# LEDBox.net
KiCad netlist of a schematic drawn in EAGLE
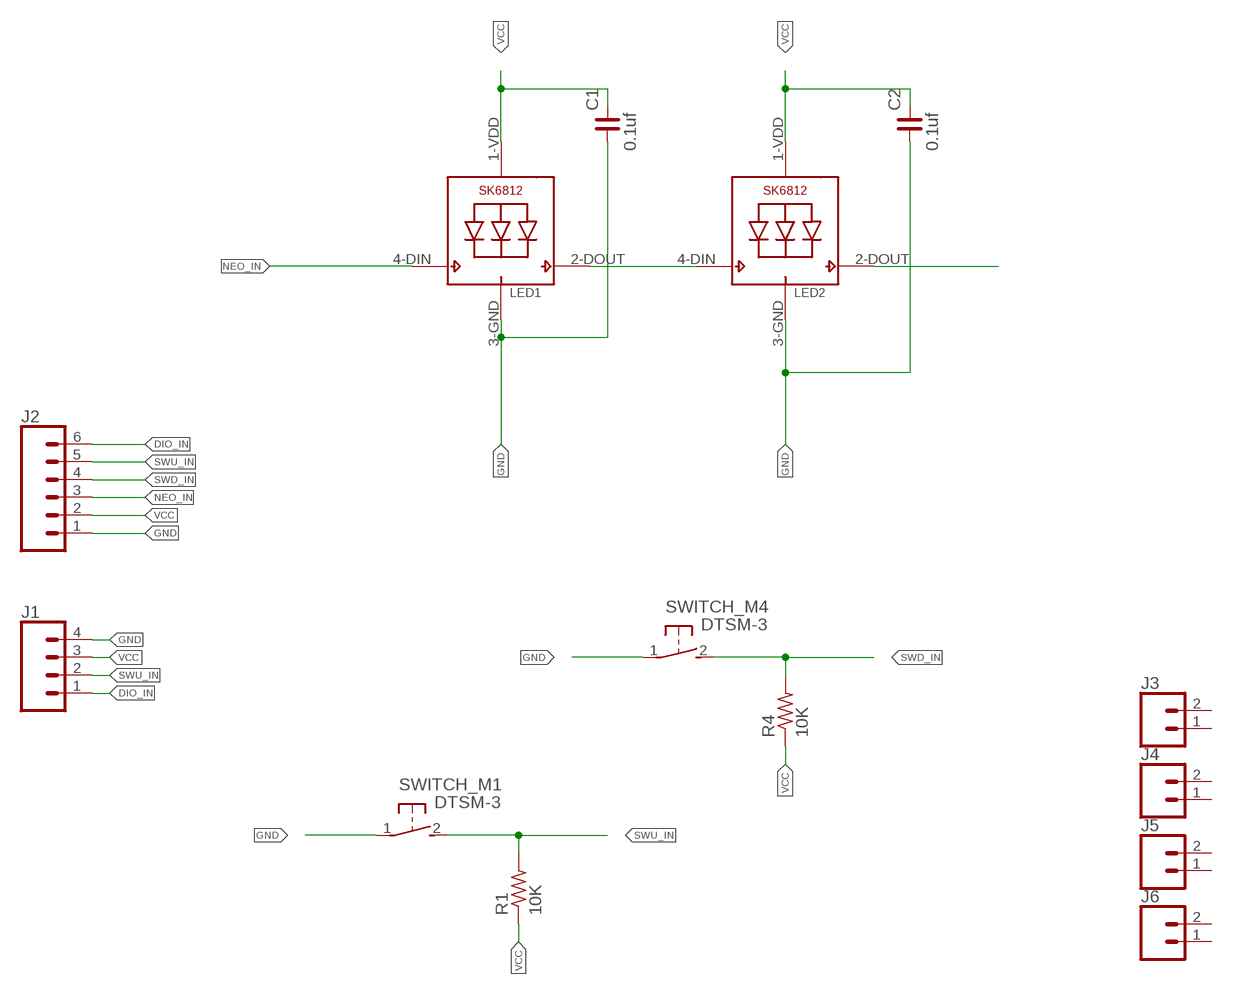
[diagram p0: schematic, sheet 1]

(export (version "E")
  (design (tool "Eeschema 10.0.6"))
  (components
    (comp (ref "C1")
      (value "0.1uf")
      (footprint "eagle-import:C0805")
      (libsource (lib "eagle-import") (part "C_0805"))
    )
    (comp (ref "C2")
      (value "0.1uf")
      (footprint "eagle-import:C0805")
      (libsource (lib "eagle-import") (part "C_0805"))
    )
    (comp (ref "J1")
      (value "CONN_041X04_NO_SILK")
      (footprint "eagle-import:1X04_NO_SILK")
      (libsource (lib "eagle-import") (part "CONN_041X04_NO_SILK"))
    )
    (comp (ref "J2")
      (value "CONN_06SMD-1MM")
      (footprint "eagle-import:1X06-1MM")
      (libsource (lib "eagle-import") (part "CONN_06SMD-1MM"))
    )
    (comp (ref "J3")
      (value "CONN_02")
      (footprint "eagle-import:1X02")
      (libsource (lib "eagle-import") (part "CONN_02"))
    )
    (comp (ref "J4")
      (value "CONN_02")
      (footprint "eagle-import:1X02")
      (libsource (lib "eagle-import") (part "CONN_02"))
    )
    (comp (ref "J5")
      (value "CONN_02")
      (footprint "eagle-import:1X02")
      (libsource (lib "eagle-import") (part "CONN_02"))
    )
    (comp (ref "J6")
      (value "CONN_02")
      (footprint "eagle-import:1X02")
      (libsource (lib "eagle-import") (part "CONN_02"))
    )
    (comp (ref "LED1")
      (value "SK6812_5050")
      (footprint "eagle-import:LED5050")
      (libsource (lib "eagle-import") (part "SK6812_5050"))
    )
    (comp (ref "LED2")
      (value "SK6812_5050")
      (footprint "eagle-import:LED5050")
      (libsource (lib "eagle-import") (part "SK6812_5050"))
    )
    (comp (ref "R1")
      (value "10K")
      (footprint "eagle-import:M0805")
      (libsource (lib "eagle-import") (part "R-US_M0805"))
    )
    (comp (ref "R4")
      (value "10K")
      (footprint "eagle-import:M0805")
      (libsource (lib "eagle-import") (part "R-US_M0805"))
    )
    (comp (ref "SWITCH_M1")
      (value "DTSM-3")
      (footprint "eagle-import:DTSM-3")
      (libsource (lib "eagle-import") (part "DTSM-3"))
    )
    (comp (ref "SWITCH_M4")
      (value "DTSM-3")
      (footprint "eagle-import:DTSM-3")
      (libsource (lib "eagle-import") (part "DTSM-3"))
    )
  )
  (nets
    (net (code "1") (name "DIO_IN") (class "Default")
      (node (ref "J1") (pin "1") (pinfunction "1_1") (pintype "passive"))
      (node (ref "J2") (pin "6") (pinfunction "6_6") (pintype "passive"))
    )
    (net (code "2") (name "GND") (class "Default")
      (node (ref "C1") (pin "1") (pinfunction "1_1") (pintype "passive"))
      (node (ref "C2") (pin "1") (pinfunction "1_1") (pintype "passive"))
      (node (ref "J1") (pin "4") (pinfunction "4_4") (pintype "passive"))
      (node (ref "J2") (pin "1") (pinfunction "1_1") (pintype "passive"))
      (node (ref "LED1") (pin "3-GND") (pinfunction "GND_3-GND") (pintype "power_in"))
      (node (ref "LED2") (pin "3-GND") (pinfunction "GND_3-GND") (pintype "power_in"))
      (node (ref "SWITCH_M1") (pin "1") (pinfunction "1_1") (pintype "passive"))
      (node (ref "SWITCH_M4") (pin "1") (pinfunction "1_1") (pintype "passive"))
    )
    (net (code "3") (name "NEO_IN") (class "Default")
      (node (ref "J2") (pin "3") (pinfunction "3_3") (pintype "passive"))
      (node (ref "LED1") (pin "4-DIN") (pinfunction "DI_4-DIN") (pintype "input"))
    )
    (net (code "4") (name "Net-(LED1-DO)") (class "Default")
      (node (ref "LED1") (pin "2-DOUT") (pinfunction "DO_2-DOUT") (pintype "output"))
      (node (ref "LED2") (pin "4-DIN") (pinfunction "DI_4-DIN") (pintype "input"))
    )
    (net (code "5") (name "SWD_IN") (class "Default")
      (node (ref "J2") (pin "4") (pinfunction "4_4") (pintype "passive"))
      (node (ref "R4") (pin "2") (pinfunction "2_2") (pintype "passive"))
      (node (ref "SWITCH_M4") (pin "2") (pinfunction "2_2") (pintype "passive"))
    )
    (net (code "6") (name "SWU_IN") (class "Default")
      (node (ref "J1") (pin "2") (pinfunction "2_2") (pintype "passive"))
      (node (ref "J2") (pin "5") (pinfunction "5_5") (pintype "passive"))
      (node (ref "R1") (pin "2") (pinfunction "2_2") (pintype "passive"))
      (node (ref "SWITCH_M1") (pin "2") (pinfunction "2_2") (pintype "passive"))
    )
    (net (code "7") (name "VCC") (class "Default")
      (node (ref "C1") (pin "2") (pinfunction "2_2") (pintype "passive"))
      (node (ref "C2") (pin "2") (pinfunction "2_2") (pintype "passive"))
      (node (ref "J1") (pin "3") (pinfunction "3_3") (pintype "passive"))
      (node (ref "J2") (pin "2") (pinfunction "2_2") (pintype "passive"))
      (node (ref "LED1") (pin "1-VDD") (pinfunction "VDD_1-VDD") (pintype "power_in"))
      (node (ref "LED2") (pin "1-VDD") (pinfunction "VDD_1-VDD") (pintype "power_in"))
      (node (ref "R1") (pin "1") (pinfunction "1_1") (pintype "passive"))
      (node (ref "R4") (pin "1") (pinfunction "1_1") (pintype "passive"))
    )
    (net (code "8") (name "unconnected-(J3-Pad1)") (class "Default")
      (node (ref "J3") (pin "1") (pinfunction "1_1") (pintype "passive"))
    )
    (net (code "9") (name "unconnected-(J3-Pad2)") (class "Default")
      (node (ref "J3") (pin "2") (pinfunction "2_2") (pintype "passive"))
    )
    (net (code "10") (name "unconnected-(J4-Pad1)") (class "Default")
      (node (ref "J4") (pin "1") (pinfunction "1_1") (pintype "passive"))
    )
    (net (code "11") (name "unconnected-(J4-Pad2)") (class "Default")
      (node (ref "J4") (pin "2") (pinfunction "2_2") (pintype "passive"))
    )
    (net (code "12") (name "unconnected-(J5-Pad1)") (class "Default")
      (node (ref "J5") (pin "1") (pinfunction "1_1") (pintype "passive"))
    )
    (net (code "13") (name "unconnected-(J5-Pad2)") (class "Default")
      (node (ref "J5") (pin "2") (pinfunction "2_2") (pintype "passive"))
    )
    (net (code "14") (name "unconnected-(J6-Pad1)") (class "Default")
      (node (ref "J6") (pin "1") (pinfunction "1_1") (pintype "passive"))
    )
    (net (code "15") (name "unconnected-(J6-Pad2)") (class "Default")
      (node (ref "J6") (pin "2") (pinfunction "2_2") (pintype "passive"))
    )
    (net (code "16") (name "unconnected-(LED2-DO-Pad2-DOUT)") (class "Default")
      (node (ref "LED2") (pin "2-DOUT") (pinfunction "DO_2-DOUT") (pintype "output"))
    )
  )
)
